# Sheet1.net
KiCad netlist of a schematic drawn in Altium Designer
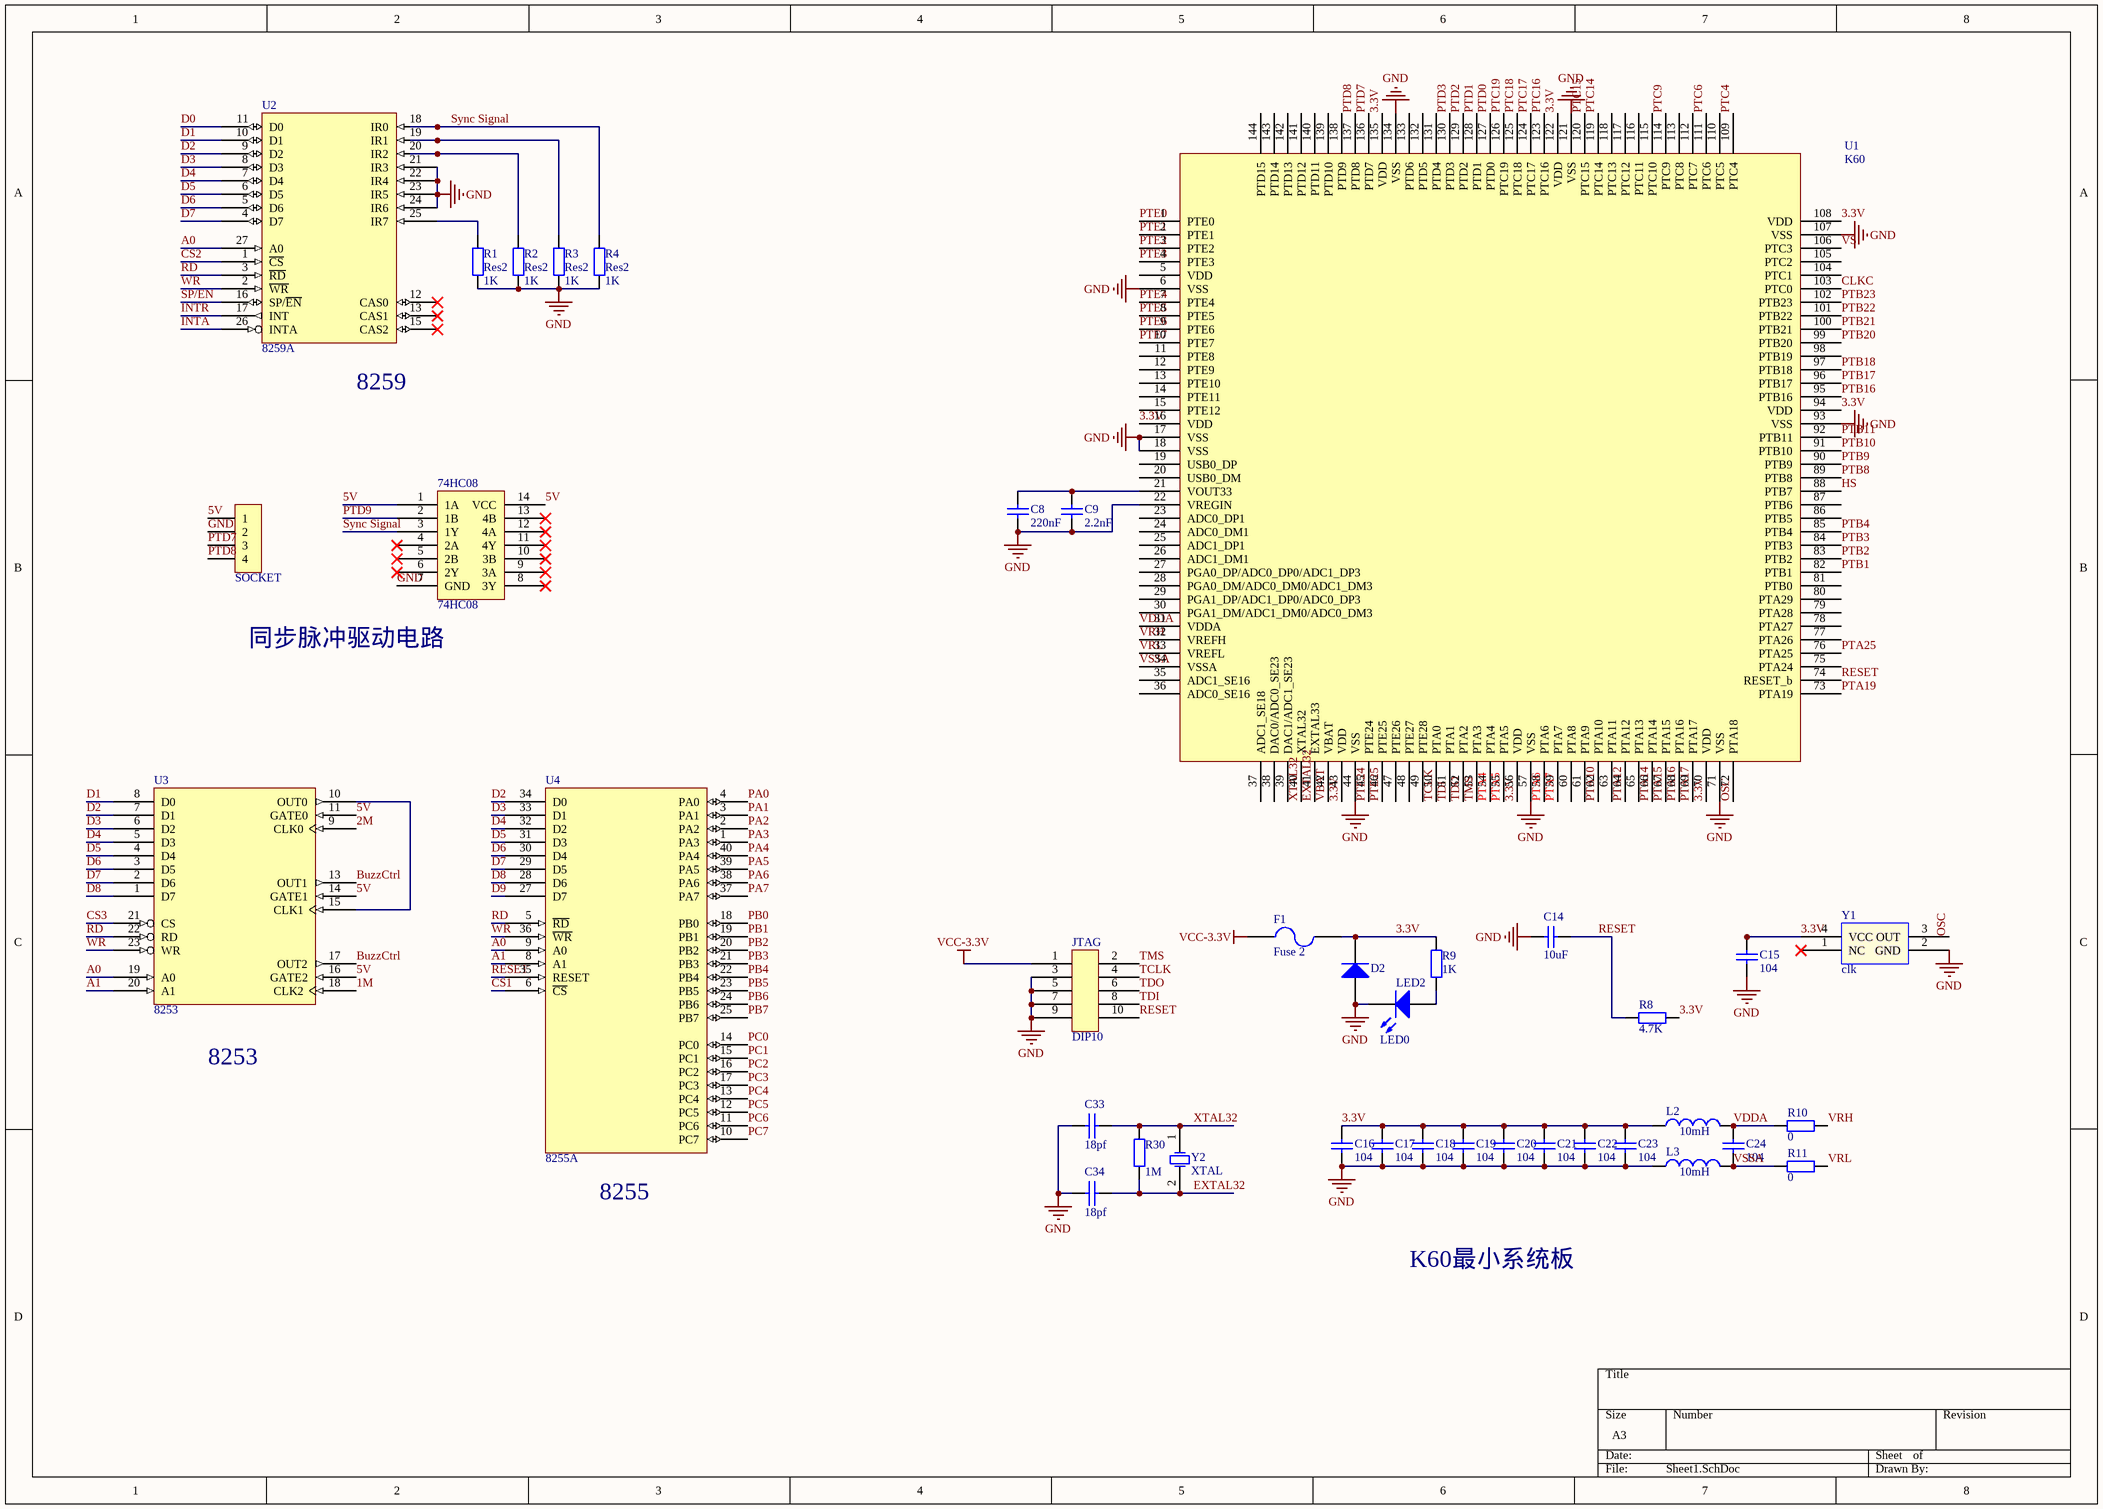
[diagram p0: Sheet1.SchDoc]

(export (version "E")
  (design (tool "Eeschema 10.0.6"))
  (components
    (comp (ref "74HC08") (value "74HC08") (footprint "SO-14") (libsource (lib "主板常用元器件") (part "74HC08")))
    (comp (ref "C8")
      (value "220nF")
      (footprint "0603")
      (description "Capacitor")
      (fields (field (name "Comment") "Cap1") (field (name "PUBLISHER") "Altium Limited"))
      (libsource (lib "主板常用元器件") (part "Cap1"))
    )
    (comp (ref "C9")
      (value "2.2nF")
      (footprint "0603")
      (description "Capacitor")
      (fields (field (name "Comment") "Cap1") (field (name "PUBLISHER") "Altium Limited"))
      (libsource (lib "主板常用元器件") (part "Cap1"))
    )
    (comp (ref "C14")
      (value "10uF")
      (footprint "0603")
      (description "Capacitor")
      (fields (field (name "Comment") "Cap1") (field (name "PUBLISHER") "Altium Limited"))
      (libsource (lib "主板常用元器件") (part "Cap1"))
    )
    (comp (ref "C15")
      (value "104")
      (footprint "0603")
      (description "Capacitor")
      (fields (field (name "Comment") "Cap1") (field (name "PUBLISHER") "Altium Limited"))
      (libsource (lib "主板常用元器件") (part "Cap1"))
    )
    (comp (ref "C16")
      (value "104")
      (footprint "0603")
      (description "Capacitor")
      (fields (field (name "Comment") "Cap1") (field (name "PUBLISHER") "Altium Limited"))
      (libsource (lib "主板常用元器件") (part "Cap1"))
    )
    (comp (ref "C17")
      (value "104")
      (footprint "0603")
      (description "Capacitor")
      (fields (field (name "Comment") "Cap1") (field (name "PUBLISHER") "Altium Limited"))
      (libsource (lib "主板常用元器件") (part "Cap1"))
    )
    (comp (ref "C18")
      (value "104")
      (footprint "0603")
      (description "Capacitor")
      (fields (field (name "Comment") "Cap1") (field (name "PUBLISHER") "Altium Limited"))
      (libsource (lib "主板常用元器件") (part "Cap1"))
    )
    (comp (ref "C19")
      (value "104")
      (footprint "0603")
      (description "Capacitor")
      (fields (field (name "Comment") "Cap1") (field (name "PUBLISHER") "Altium Limited"))
      (libsource (lib "主板常用元器件") (part "Cap1"))
    )
    (comp (ref "C20")
      (value "104")
      (footprint "0603")
      (description "Capacitor")
      (fields (field (name "Comment") "Cap1") (field (name "PUBLISHER") "Altium Limited"))
      (libsource (lib "主板常用元器件") (part "Cap1"))
    )
    (comp (ref "C21")
      (value "104")
      (footprint "0603")
      (description "Capacitor")
      (fields (field (name "Comment") "Cap1") (field (name "PUBLISHER") "Altium Limited"))
      (libsource (lib "主板常用元器件") (part "Cap1"))
    )
    (comp (ref "C22")
      (value "104")
      (footprint "0603")
      (description "Capacitor")
      (fields (field (name "Comment") "Cap1") (field (name "PUBLISHER") "Altium Limited"))
      (libsource (lib "主板常用元器件") (part "Cap1"))
    )
    (comp (ref "C23")
      (value "104")
      (footprint "0603")
      (description "Capacitor")
      (fields (field (name "Comment") "Cap1") (field (name "PUBLISHER") "Altium Limited"))
      (libsource (lib "主板常用元器件") (part "Cap1"))
    )
    (comp (ref "C24")
      (value "104")
      (footprint "0603")
      (description "Capacitor")
      (fields (field (name "Comment") "Cap1") (field (name "PUBLISHER") "Altium Limited"))
      (libsource (lib "主板常用元器件") (part "Cap1"))
    )
    (comp (ref "C33")
      (value "18pf")
      (footprint "0603")
      (description "Capacitor")
      (libsource (lib "easy335schlib") (part "CAP"))
    )
    (comp (ref "C34")
      (value "18pf")
      (footprint "0603")
      (description "Capacitor")
      (libsource (lib "easy335schlib") (part "CAP"))
    )
    (comp (ref "D2")
      (value "Diode")
      (footprint "1206")
      (description "Default Diode")
      (fields (field (name "PUBLISHER") "Altium Limited"))
      (libsource (lib "Miscellaneous Devices") (part "Diode"))
    )
    (comp (ref "F1")
      (value "Fuse 2")
      (footprint "1206")
      (description "Fuse")
      (fields (field (name "PUBLISHER") "Altium Limited"))
      (libsource (lib "Miscellaneous Devices") (part "Fuse 2"))
    )
    (comp (ref "JTAG") (value "DIP10") (footprint "IDC-10") (libsource (lib "主板常用元器件") (part "DIP10")))
    (comp (ref "L2")
      (value "10mH")
      (footprint "0805")
      (description "Inductor")
      (fields (field (name "PUBLISHER") "Altium Limited"))
      (libsource (lib "Miscellaneous Devices") (part "Inductor"))
    )
    (comp (ref "L3")
      (value "10mH")
      (footprint "0805")
      (description "Inductor")
      (fields (field (name "PUBLISHER") "Altium Limited"))
      (libsource (lib "Miscellaneous Devices") (part "Inductor"))
    )
    (comp (ref "LED2")
      (value "LED0")
      (footprint "0603")
      (description "Typical INFRARED GaAs LED")
      (fields (field (name "PUBLISHER") "Altium Limited"))
      (libsource (lib "Miscellaneous Devices") (part "LED0"))
    )
    (comp (ref "R1")
      (value "Res2")
      (footprint "AXIAL-0.4")
      (description "Resistor")
      (fields (field (name "ALTIUM_VALUE") "1K") (field (name "PUBLISHER") "Altium Limited"))
      (libsource (lib "Miscellaneous Devices") (part "Res2"))
    )
    (comp (ref "R2")
      (value "Res2")
      (footprint "AXIAL-0.4")
      (description "Resistor")
      (fields (field (name "ALTIUM_VALUE") "1K") (field (name "PUBLISHER") "Altium Limited"))
      (libsource (lib "Miscellaneous Devices") (part "Res2"))
    )
    (comp (ref "R3")
      (value "Res2")
      (footprint "AXIAL-0.4")
      (description "Resistor")
      (fields (field (name "ALTIUM_VALUE") "1K") (field (name "PUBLISHER") "Altium Limited"))
      (libsource (lib "Miscellaneous Devices") (part "Res2"))
    )
    (comp (ref "R4")
      (value "Res2")
      (footprint "AXIAL-0.4")
      (description "Resistor")
      (fields (field (name "ALTIUM_VALUE") "1K") (field (name "PUBLISHER") "Altium Limited"))
      (libsource (lib "Miscellaneous Devices") (part "Res2"))
    )
    (comp (ref "R8")
      (value "4.7K")
      (footprint "0603")
      (description "Resistor")
      (fields (field (name "Comment") "Res2") (field (name "PUBLISHER") "Altium Limited"))
      (libsource (lib "") (part "Res2_1"))
    )
    (comp (ref "R9")
      (value "1K")
      (footprint "0603")
      (description "Resistor")
      (fields (field (name "Comment") "Res2") (field (name "PUBLISHER") "Altium Limited"))
      (libsource (lib "主板常用元器件") (part "Res2"))
    )
    (comp (ref "R10")
      (value "0")
      (footprint "0603")
      (description "Resistor")
      (fields (field (name "Comment") "Res2") (field (name "PUBLISHER") "Altium Limited"))
      (libsource (lib "") (part "Res2_1"))
    )
    (comp (ref "R11")
      (value "0")
      (footprint "0603")
      (description "Resistor")
      (fields (field (name "Comment") "Res2") (field (name "PUBLISHER") "Altium Limited"))
      (libsource (lib "") (part "Res2_1"))
    )
    (comp (ref "R30")
      (value "1M")
      (footprint "0603")
      (description "Resistor")
      (fields (field (name "Comment") "Res2") (field (name "PUBLISHER") "Altium Limited"))
      (libsource (lib "Miscellaneous Devices") (part "Res2"))
    )
    (comp (ref "U1") (value "K60") (footprint "K60_QFP144") (libsource (lib "*") (part "K60")))
    (comp (ref "U2") (value "8259A") (libsource (lib "Intel 1991-1992") (part "8259A")))
    (comp (ref "U3") (value "8253") (footprint "DIP-24") (libsource (lib "Intel 1991-1992") (part "8253")))
    (comp (ref "U4") (value "8255A") (footprint "DIP-40") (libsource (lib "Intel 1991-1992") (part "8255A")))
    (comp (ref "Y1") (value "clk") (footprint "5032") (libsource (lib "*") (part "clk")))
    (comp (ref "Y2")
      (value "XTAL")
      (footprint "晶振-壳")
      (description "Crystal Oscillator")
      (fields (field (name "PUBLISHER") "Altium Limited"))
      (libsource (lib "Miscellaneous Devices") (part "XTAL"))
    )
    (comp (ref "YY") (value "SOCKET") (footprint "SIP4") (libsource (lib "主板常用元器件") (part "CON4")))
  )
  (nets
    (net (code "1") (name "/1M") (class "Default")
      (node (ref "U3") (pin "18") (pinfunction "CLK2_18") (pintype "input"))
    )
    (net (code "2") (name "/2M") (class "Default")
      (node (ref "U3") (pin "9") (pinfunction "CLK0_9") (pintype "input"))
    )
    (net (code "3") (name "/3.3V") (class "Default")
      (node (ref "C15") (pin "1") (pinfunction "1_1") (pintype "passive"))
      (node (ref "C16") (pin "1") (pinfunction "1_1") (pintype "passive"))
      (node (ref "C17") (pin "1") (pinfunction "1_1") (pintype "passive"))
      (node (ref "C18") (pin "1") (pinfunction "1_1") (pintype "passive"))
      (node (ref "C19") (pin "1") (pinfunction "1_1") (pintype "passive"))
      (node (ref "C20") (pin "1") (pinfunction "1_1") (pintype "passive"))
      (node (ref "C21") (pin "1") (pinfunction "1_1") (pintype "passive"))
      (node (ref "C22") (pin "1") (pinfunction "1_1") (pintype "passive"))
      (node (ref "C23") (pin "1") (pinfunction "1_1") (pintype "passive"))
      (node (ref "D2") (pin "2") (pinfunction "K_2") (pintype "passive"))
      (node (ref "F1") (pin "2") (pinfunction "2_2") (pintype "passive"))
      (node (ref "L2") (pin "1") (pinfunction "1_1") (pintype "passive"))
      (node (ref "R8") (pin "1") (pinfunction "1_1") (pintype "passive"))
      (node (ref "R9") (pin "1") (pinfunction "1_1") (pintype "passive"))
      (node (ref "U1") (pin "108") (pinfunction "VDD_108") (pintype "passive"))
      (node (ref "U1") (pin "122") (pinfunction "VDD_122") (pintype "passive"))
      (node (ref "U1") (pin "135") (pinfunction "VDD_135") (pintype "passive"))
      (node (ref "U1") (pin "16") (pinfunction "VDD_16") (pintype "passive"))
      (node (ref "U1") (pin "43") (pinfunction "VDD_43") (pintype "passive"))
      (node (ref "U1") (pin "56") (pinfunction "VDD_56") (pintype "passive"))
      (node (ref "U1") (pin "70") (pinfunction "VDD_70") (pintype "passive"))
      (node (ref "U1") (pin "94") (pinfunction "VDD_94") (pintype "passive"))
      (node (ref "Y1") (pin "4") (pinfunction "VCC_4") (pintype "passive"))
    )
    (net (code "4") (name "/5V") (class "Default")
      (node (ref "74HC08") (pin "1") (pinfunction "1A_1") (pintype "passive"))
      (node (ref "74HC08") (pin "14") (pinfunction "VCC_14") (pintype "passive"))
      (node (ref "U3") (pin "11") (pinfunction "GATE0_11") (pintype "input"))
      (node (ref "U3") (pin "14") (pinfunction "GATE1_14") (pintype "input"))
      (node (ref "U3") (pin "16") (pinfunction "GATE2_16") (pintype "input"))
      (node (ref "YY") (pin "1") (pinfunction "1_1") (pintype "passive"))
    )
    (net (code "5") (name "/A0") (class "Default")
      (node (ref "U2") (pin "27") (pinfunction "A0_27") (pintype "input"))
      (node (ref "U3") (pin "19") (pinfunction "A0_19") (pintype "input"))
      (node (ref "U4") (pin "9") (pinfunction "A0_9") (pintype "input"))
    )
    (net (code "6") (name "/A1") (class "Default")
      (node (ref "U3") (pin "20") (pinfunction "A1_20") (pintype "input"))
      (node (ref "U4") (pin "8") (pinfunction "A1_8") (pintype "input"))
    )
    (net (code "7") (name "/BuzzCtrl") (class "Default")
      (node (ref "U3") (pin "13") (pinfunction "OUT1_13") (pintype "output"))
      (node (ref "U3") (pin "17") (pinfunction "OUT2_17") (pintype "output"))
    )
    (net (code "8") (name "/CLKC") (class "Default")
      (node (ref "U1") (pin "103") (pinfunction "PTC0_103") (pintype "passive"))
    )
    (net (code "9") (name "/CS1") (class "Default")
      (node (ref "U4") (pin "6") (pinfunction "~{CS}_6") (pintype "input"))
    )
    (net (code "10") (name "/CS2") (class "Default")
      (node (ref "U2") (pin "1") (pinfunction "~{CS}_1") (pintype "input"))
    )
    (net (code "11") (name "/CS3") (class "Default")
      (node (ref "U3") (pin "21") (pinfunction "CS_21") (pintype "input"))
    )
    (net (code "12") (name "/D0") (class "Default")
      (node (ref "U2") (pin "11") (pinfunction "D0_11") (pintype "bidirectional"))
    )
    (net (code "13") (name "/D1") (class "Default")
      (node (ref "U2") (pin "10") (pinfunction "D1_10") (pintype "bidirectional"))
      (node (ref "U3") (pin "8") (pinfunction "D0_8") (pintype "tri_state"))
    )
    (net (code "14") (name "/D2") (class "Default")
      (node (ref "U2") (pin "9") (pinfunction "D2_9") (pintype "bidirectional"))
      (node (ref "U3") (pin "7") (pinfunction "D1_7") (pintype "tri_state"))
      (node (ref "U4") (pin "34") (pinfunction "D0_34") (pintype "tri_state"))
    )
    (net (code "15") (name "/D3") (class "Default")
      (node (ref "U2") (pin "8") (pinfunction "D3_8") (pintype "bidirectional"))
      (node (ref "U3") (pin "6") (pinfunction "D2_6") (pintype "tri_state"))
      (node (ref "U4") (pin "33") (pinfunction "D1_33") (pintype "tri_state"))
    )
    (net (code "16") (name "/D4") (class "Default")
      (node (ref "U2") (pin "7") (pinfunction "D4_7") (pintype "bidirectional"))
      (node (ref "U3") (pin "5") (pinfunction "D3_5") (pintype "tri_state"))
      (node (ref "U4") (pin "32") (pinfunction "D2_32") (pintype "tri_state"))
    )
    (net (code "17") (name "/D5") (class "Default")
      (node (ref "U2") (pin "6") (pinfunction "D5_6") (pintype "bidirectional"))
      (node (ref "U3") (pin "4") (pinfunction "D4_4") (pintype "tri_state"))
      (node (ref "U4") (pin "31") (pinfunction "D3_31") (pintype "tri_state"))
    )
    (net (code "18") (name "/D6") (class "Default")
      (node (ref "U2") (pin "5") (pinfunction "D6_5") (pintype "bidirectional"))
      (node (ref "U3") (pin "3") (pinfunction "D5_3") (pintype "tri_state"))
      (node (ref "U4") (pin "30") (pinfunction "D4_30") (pintype "tri_state"))
    )
    (net (code "19") (name "/D7") (class "Default")
      (node (ref "U2") (pin "4") (pinfunction "D7_4") (pintype "bidirectional"))
      (node (ref "U3") (pin "2") (pinfunction "D6_2") (pintype "tri_state"))
      (node (ref "U4") (pin "29") (pinfunction "D5_29") (pintype "tri_state"))
    )
    (net (code "20") (name "/D8") (class "Default")
      (node (ref "U3") (pin "1") (pinfunction "D7_1") (pintype "tri_state"))
      (node (ref "U4") (pin "28") (pinfunction "D6_28") (pintype "tri_state"))
    )
    (net (code "21") (name "/D9") (class "Default")
      (node (ref "U4") (pin "27") (pinfunction "D7_27") (pintype "tri_state"))
    )
    (net (code "22") (name "/EXTAL32") (class "Default")
      (node (ref "C34") (pin "2") (pinfunction "2_2") (pintype "passive"))
      (node (ref "R30") (pin "1") (pinfunction "1_1") (pintype "passive"))
      (node (ref "U1") (pin "41") (pinfunction "EXTAL33_41") (pintype "passive"))
      (node (ref "Y2") (pin "2") (pinfunction "OSC2_2") (pintype "passive"))
    )
    (net (code "23") (name "/HS") (class "Default")
      (node (ref "U1") (pin "88") (pinfunction "PTB7_88") (pintype "passive"))
    )
    (net (code "24") (name "/INTA") (class "Default")
      (node (ref "U2") (pin "26") (pinfunction "INTA_26") (pintype "input"))
    )
    (net (code "25") (name "/INTR") (class "Default")
      (node (ref "U2") (pin "17") (pinfunction "INT_17") (pintype "output"))
    )
    (net (code "26") (name "/OSC") (class "Default")
      (node (ref "U1") (pin "72") (pinfunction "PTA18_72") (pintype "passive"))
      (node (ref "Y1") (pin "3") (pinfunction "OUT_3") (pintype "passive"))
    )
    (net (code "27") (name "/PA0") (class "Default")
      (node (ref "U4") (pin "4") (pinfunction "PA0_4") (pintype "bidirectional"))
    )
    (net (code "28") (name "/PA1") (class "Default")
      (node (ref "U4") (pin "3") (pinfunction "PA1_3") (pintype "bidirectional"))
    )
    (net (code "29") (name "/PA2") (class "Default")
      (node (ref "U4") (pin "2") (pinfunction "PA2_2") (pintype "bidirectional"))
    )
    (net (code "30") (name "/PA3") (class "Default")
      (node (ref "U4") (pin "1") (pinfunction "PA3_1") (pintype "bidirectional"))
    )
    (net (code "31") (name "/PA4") (class "Default")
      (node (ref "U4") (pin "40") (pinfunction "PA4_40") (pintype "bidirectional"))
    )
    (net (code "32") (name "/PA5") (class "Default")
      (node (ref "U4") (pin "39") (pinfunction "PA5_39") (pintype "bidirectional"))
    )
    (net (code "33") (name "/PA6") (class "Default")
      (node (ref "U4") (pin "38") (pinfunction "PA6_38") (pintype "bidirectional"))
    )
    (net (code "34") (name "/PA7") (class "Default")
      (node (ref "U4") (pin "37") (pinfunction "PA7_37") (pintype "bidirectional"))
    )
    (net (code "35") (name "/PB0") (class "Default")
      (node (ref "U4") (pin "18") (pinfunction "PB0_18") (pintype "bidirectional"))
    )
    (net (code "36") (name "/PB1") (class "Default")
      (node (ref "U4") (pin "19") (pinfunction "PB1_19") (pintype "bidirectional"))
    )
    (net (code "37") (name "/PB2") (class "Default")
      (node (ref "U4") (pin "20") (pinfunction "PB2_20") (pintype "bidirectional"))
    )
    (net (code "38") (name "/PB3") (class "Default")
      (node (ref "U4") (pin "21") (pinfunction "PB3_21") (pintype "bidirectional"))
    )
    (net (code "39") (name "/PB4") (class "Default")
      (node (ref "U4") (pin "22") (pinfunction "PB4_22") (pintype "bidirectional"))
    )
    (net (code "40") (name "/PB5") (class "Default")
      (node (ref "U4") (pin "23") (pinfunction "PB5_23") (pintype "bidirectional"))
    )
    (net (code "41") (name "/PB6") (class "Default")
      (node (ref "U4") (pin "24") (pinfunction "PB6_24") (pintype "bidirectional"))
    )
    (net (code "42") (name "/PB7") (class "Default")
      (node (ref "U4") (pin "25") (pinfunction "PB7_25") (pintype "bidirectional"))
    )
    (net (code "43") (name "/PC0") (class "Default")
      (node (ref "U4") (pin "14") (pinfunction "PC0_14") (pintype "bidirectional"))
    )
    (net (code "44") (name "/PC1") (class "Default")
      (node (ref "U4") (pin "15") (pinfunction "PC1_15") (pintype "bidirectional"))
    )
    (net (code "45") (name "/PC2") (class "Default")
      (node (ref "U4") (pin "16") (pinfunction "PC2_16") (pintype "bidirectional"))
    )
    (net (code "46") (name "/PC3") (class "Default")
      (node (ref "U4") (pin "17") (pinfunction "PC3_17") (pintype "bidirectional"))
    )
    (net (code "47") (name "/PC4") (class "Default")
      (node (ref "U4") (pin "13") (pinfunction "PC4_13") (pintype "bidirectional"))
    )
    (net (code "48") (name "/PC5") (class "Default")
      (node (ref "U4") (pin "12") (pinfunction "PC5_12") (pintype "bidirectional"))
    )
    (net (code "49") (name "/PC6") (class "Default")
      (node (ref "U4") (pin "11") (pinfunction "PC6_11") (pintype "bidirectional"))
    )
    (net (code "50") (name "/PC7") (class "Default")
      (node (ref "U4") (pin "10") (pinfunction "PC7_10") (pintype "bidirectional"))
    )
    (net (code "51") (name "/PTA4") (class "Default")
      (node (ref "U1") (pin "54") (pinfunction "PTA4_54") (pintype "passive"))
    )
    (net (code "52") (name "/PTA5") (class "Default")
      (node (ref "U1") (pin "55") (pinfunction "PTA5_55") (pintype "passive"))
    )
    (net (code "53") (name "/PTA6") (class "Default")
      (node (ref "U1") (pin "58") (pinfunction "PTA6_58") (pintype "passive"))
    )
    (net (code "54") (name "/PTA7") (class "Default")
      (node (ref "U1") (pin "59") (pinfunction "PTA7_59") (pintype "passive"))
    )
    (net (code "55") (name "/PTA10") (class "Default")
      (node (ref "U1") (pin "62") (pinfunction "PTA10_62") (pintype "passive"))
    )
    (net (code "56") (name "/PTA12") (class "Default")
      (node (ref "U1") (pin "64") (pinfunction "PTA12_64") (pintype "passive"))
    )
    (net (code "57") (name "/PTA14") (class "Default")
      (node (ref "U1") (pin "66") (pinfunction "PTA14_66") (pintype "passive"))
    )
    (net (code "58") (name "/PTA15") (class "Default")
      (node (ref "U1") (pin "67") (pinfunction "PTA15_67") (pintype "passive"))
    )
    (net (code "59") (name "/PTA16") (class "Default")
      (node (ref "U1") (pin "68") (pinfunction "PTA16_68") (pintype "passive"))
    )
    (net (code "60") (name "/PTA17") (class "Default")
      (node (ref "U1") (pin "69") (pinfunction "PTA17_69") (pintype "passive"))
    )
    (net (code "61") (name "/PTA19") (class "Default")
      (node (ref "U1") (pin "73") (pinfunction "PTA19_73") (pintype "passive"))
    )
    (net (code "62") (name "/PTA25") (class "Default")
      (node (ref "U1") (pin "76") (pinfunction "PTA25_76") (pintype "passive"))
    )
    (net (code "63") (name "/PTB1") (class "Default")
      (node (ref "U1") (pin "82") (pinfunction "PTB1_82") (pintype "passive"))
    )
    (net (code "64") (name "/PTB2") (class "Default")
      (node (ref "U1") (pin "83") (pinfunction "PTB2_83") (pintype "passive"))
    )
    (net (code "65") (name "/PTB3") (class "Default")
      (node (ref "U1") (pin "84") (pinfunction "PTB3_84") (pintype "passive"))
    )
    (net (code "66") (name "/PTB4") (class "Default")
      (node (ref "U1") (pin "85") (pinfunction "PTB4_85") (pintype "passive"))
    )
    (net (code "67") (name "/PTB8") (class "Default")
      (node (ref "U1") (pin "89") (pinfunction "PTB8_89") (pintype "passive"))
    )
    (net (code "68") (name "/PTB9") (class "Default")
      (node (ref "U1") (pin "90") (pinfunction "PTB9_90") (pintype "passive"))
    )
    (net (code "69") (name "/PTB10") (class "Default")
      (node (ref "U1") (pin "91") (pinfunction "PTB10_91") (pintype "passive"))
    )
    (net (code "70") (name "/PTB11") (class "Default")
      (node (ref "U1") (pin "92") (pinfunction "PTB11_92") (pintype "passive"))
    )
    (net (code "71") (name "/PTB16") (class "Default")
      (node (ref "U1") (pin "95") (pinfunction "PTB16_95") (pintype "passive"))
    )
    (net (code "72") (name "/PTB17") (class "Default")
      (node (ref "U1") (pin "96") (pinfunction "PTB17_96") (pintype "passive"))
    )
    (net (code "73") (name "/PTB18") (class "Default")
      (node (ref "U1") (pin "97") (pinfunction "PTB18_97") (pintype "passive"))
    )
    (net (code "74") (name "/PTB20") (class "Default")
      (node (ref "U1") (pin "99") (pinfunction "PTB20_99") (pintype "passive"))
    )
    (net (code "75") (name "/PTB21") (class "Default")
      (node (ref "U1") (pin "100") (pinfunction "PTB21_100") (pintype "passive"))
    )
    (net (code "76") (name "/PTB22") (class "Default")
      (node (ref "U1") (pin "101") (pinfunction "PTB22_101") (pintype "passive"))
    )
    (net (code "77") (name "/PTB23") (class "Default")
      (node (ref "U1") (pin "102") (pinfunction "PTB23_102") (pintype "passive"))
    )
    (net (code "78") (name "/PTC4") (class "Default")
      (node (ref "U1") (pin "109") (pinfunction "PTC4_109") (pintype "passive"))
    )
    (net (code "79") (name "/PTC6") (class "Default")
      (node (ref "U1") (pin "111") (pinfunction "PTC6_111") (pintype "passive"))
    )
    (net (code "80") (name "/PTC9") (class "Default")
      (node (ref "U1") (pin "114") (pinfunction "PTC9_114") (pintype "passive"))
    )
    (net (code "81") (name "/PTC14") (class "Default")
      (node (ref "U1") (pin "119") (pinfunction "PTC14_119") (pintype "passive"))
    )
    (net (code "82") (name "/PTC15") (class "Default")
      (node (ref "U1") (pin "120") (pinfunction "PTC15_120") (pintype "passive"))
    )
    (net (code "83") (name "/PTC16") (class "Default")
      (node (ref "U1") (pin "123") (pinfunction "PTC16_123") (pintype "passive"))
    )
    (net (code "84") (name "/PTC17") (class "Default")
      (node (ref "U1") (pin "124") (pinfunction "PTC17_124") (pintype "passive"))
    )
    (net (code "85") (name "/PTC18") (class "Default")
      (node (ref "U1") (pin "125") (pinfunction "PTC18_125") (pintype "passive"))
    )
    (net (code "86") (name "/PTC19") (class "Default")
      (node (ref "U1") (pin "126") (pinfunction "PTC19_126") (pintype "passive"))
    )
    (net (code "87") (name "/PTD0") (class "Default")
      (node (ref "U1") (pin "127") (pinfunction "PTD0_127") (pintype "passive"))
    )
    (net (code "88") (name "/PTD1") (class "Default")
      (node (ref "U1") (pin "128") (pinfunction "PTD1_128") (pintype "passive"))
    )
    (net (code "89") (name "/PTD2") (class "Default")
      (node (ref "U1") (pin "129") (pinfunction "PTD2_129") (pintype "passive"))
    )
    (net (code "90") (name "/PTD3") (class "Default")
      (node (ref "U1") (pin "130") (pinfunction "PTD3_130") (pintype "passive"))
    )
    (net (code "91") (name "/PTD7") (class "Default")
      (node (ref "U1") (pin "136") (pinfunction "PTD7_136") (pintype "passive"))
      (node (ref "YY") (pin "3") (pinfunction "3_3") (pintype "passive"))
    )
    (net (code "92") (name "/PTD8") (class "Default")
      (node (ref "U1") (pin "137") (pinfunction "PTD8_137") (pintype "passive"))
      (node (ref "YY") (pin "4") (pinfunction "4_4") (pintype "passive"))
    )
    (net (code "93") (name "/PTD9") (class "Default")
      (node (ref "74HC08") (pin "2") (pinfunction "1B_2") (pintype "passive"))
    )
    (net (code "94") (name "/PTE0") (class "Default")
      (node (ref "U1") (pin "1") (pinfunction "PTE0_1") (pintype "passive"))
    )
    (net (code "95") (name "/PTE1") (class "Default")
      (node (ref "U1") (pin "2") (pinfunction "PTE1_2") (pintype "passive"))
    )
    (net (code "96") (name "/PTE2") (class "Default")
      (node (ref "U1") (pin "3") (pinfunction "PTE2_3") (pintype "passive"))
    )
    (net (code "97") (name "/PTE3") (class "Default")
      (node (ref "U1") (pin "4") (pinfunction "PTE3_4") (pintype "passive"))
    )
    (net (code "98") (name "/PTE4") (class "Default")
      (node (ref "U1") (pin "7") (pinfunction "PTE4_7") (pintype "passive"))
    )
    (net (code "99") (name "/PTE5") (class "Default")
      (node (ref "U1") (pin "8") (pinfunction "PTE5_8") (pintype "passive"))
    )
    (net (code "100") (name "/PTE6") (class "Default")
      (node (ref "U1") (pin "9") (pinfunction "PTE6_9") (pintype "passive"))
    )
    (net (code "101") (name "/PTE7") (class "Default")
      (node (ref "U1") (pin "10") (pinfunction "PTE7_10") (pintype "passive"))
    )
    (net (code "102") (name "/PTE24") (class "Default")
      (node (ref "U1") (pin "45") (pinfunction "PTE24_45") (pintype "passive"))
    )
    (net (code "103") (name "/PTE25") (class "Default")
      (node (ref "U1") (pin "46") (pinfunction "PTE25_46") (pintype "passive"))
    )
    (net (code "104") (name "/RD") (class "Default")
      (node (ref "U2") (pin "3") (pinfunction "~{RD}_3") (pintype "input"))
      (node (ref "U3") (pin "22") (pinfunction "RD_22") (pintype "input"))
      (node (ref "U4") (pin "5") (pinfunction "~{RD}_5") (pintype "input"))
    )
    (net (code "105") (name "/RESET") (class "Default")
      (node (ref "C14") (pin "2") (pinfunction "2_2") (pintype "passive"))
      (node (ref "JTAG") (pin "10") (pinfunction "10_10") (pintype "passive"))
      (node (ref "R8") (pin "2") (pinfunction "2_2") (pintype "passive"))
      (node (ref "U1") (pin "74") (pinfunction "RESET_b_74") (pintype "passive"))
      (node (ref "U4") (pin "35") (pinfunction "RESET_35") (pintype "input"))
    )
    (net (code "106") (name "/SP{slash}EN") (class "Default")
      (node (ref "U2") (pin "16") (pinfunction "SP/~{EN}_16") (pintype "bidirectional"))
    )
    (net (code "107") (name "/Sync Signal") (class "Default")
      (node (ref "74HC08") (pin "3") (pinfunction "1Y_3") (pintype "passive"))
      (node (ref "R4") (pin "2") (pinfunction "2_2") (pintype "passive"))
      (node (ref "U2") (pin "18") (pinfunction "IR0_18") (pintype "input"))
    )
    (net (code "108") (name "/TCLK") (class "Default")
      (node (ref "JTAG") (pin "4") (pinfunction "4_4") (pintype "passive"))
      (node (ref "U1") (pin "50") (pinfunction "PTA0_50") (pintype "passive"))
    )
    (net (code "109") (name "/TDI") (class "Default")
      (node (ref "JTAG") (pin "8") (pinfunction "8_8") (pintype "passive"))
      (node (ref "U1") (pin "51") (pinfunction "PTA1_51") (pintype "passive"))
    )
    (net (code "110") (name "/TDO") (class "Default")
      (node (ref "JTAG") (pin "6") (pinfunction "6_6") (pintype "passive"))
      (node (ref "U1") (pin "52") (pinfunction "PTA2_52") (pintype "passive"))
    )
    (net (code "111") (name "/TMS") (class "Default")
      (node (ref "JTAG") (pin "2") (pinfunction "2_2") (pintype "passive"))
      (node (ref "U1") (pin "53") (pinfunction "PTA3_53") (pintype "passive"))
    )
    (net (code "112") (name "/VBAT") (class "Default")
      (node (ref "U1") (pin "42") (pinfunction "VBAT_42") (pintype "passive"))
    )
    (net (code "113") (name "/VDDA") (class "Default")
      (node (ref "C24") (pin "1") (pinfunction "1_1") (pintype "passive"))
      (node (ref "L2") (pin "2") (pinfunction "2_2") (pintype "passive"))
      (node (ref "R10") (pin "2") (pinfunction "2_2") (pintype "passive"))
      (node (ref "U1") (pin "31") (pinfunction "VDDA_31") (pintype "passive"))
    )
    (net (code "114") (name "/VRH") (class "Default")
      (node (ref "R10") (pin "1") (pinfunction "1_1") (pintype "passive"))
      (node (ref "U1") (pin "32") (pinfunction "VREFH_32") (pintype "passive"))
    )
    (net (code "115") (name "/VRL") (class "Default")
      (node (ref "R11") (pin "1") (pinfunction "1_1") (pintype "passive"))
      (node (ref "U1") (pin "33") (pinfunction "VREFL_33") (pintype "passive"))
    )
    (net (code "116") (name "/VS") (class "Default")
      (node (ref "U1") (pin "106") (pinfunction "PTC3_106") (pintype "passive"))
    )
    (net (code "117") (name "/VSSA") (class "Default")
      (node (ref "C24") (pin "2") (pinfunction "2_2") (pintype "passive"))
      (node (ref "L3") (pin "2") (pinfunction "2_2") (pintype "passive"))
      (node (ref "R11") (pin "2") (pinfunction "2_2") (pintype "passive"))
      (node (ref "U1") (pin "34") (pinfunction "VSSA_34") (pintype "passive"))
    )
    (net (code "118") (name "/WR") (class "Default")
      (node (ref "U2") (pin "2") (pinfunction "~{WR}_2") (pintype "input"))
      (node (ref "U3") (pin "23") (pinfunction "WR_23") (pintype "input"))
      (node (ref "U4") (pin "36") (pinfunction "~{WR}_36") (pintype "input"))
    )
    (net (code "119") (name "/XTAL32") (class "Default")
      (node (ref "C33") (pin "2") (pinfunction "2_2") (pintype "passive"))
      (node (ref "R30") (pin "2") (pinfunction "2_2") (pintype "passive"))
      (node (ref "U1") (pin "40") (pinfunction "XTAL32_40") (pintype "passive"))
      (node (ref "Y2") (pin "1") (pinfunction "OSC1_1") (pintype "passive"))
    )
    (net (code "120") (name "GND") (class "Default")
      (node (ref "74HC08") (pin "7") (pinfunction "GND_7") (pintype "passive"))
      (node (ref "C14") (pin "1") (pinfunction "1_1") (pintype "passive"))
      (node (ref "C15") (pin "2") (pinfunction "2_2") (pintype "passive"))
      (node (ref "C16") (pin "2") (pinfunction "2_2") (pintype "passive"))
      (node (ref "C17") (pin "2") (pinfunction "2_2") (pintype "passive"))
      (node (ref "C18") (pin "2") (pinfunction "2_2") (pintype "passive"))
      (node (ref "C19") (pin "2") (pinfunction "2_2") (pintype "passive"))
      (node (ref "C20") (pin "2") (pinfunction "2_2") (pintype "passive"))
      (node (ref "C21") (pin "2") (pinfunction "2_2") (pintype "passive"))
      (node (ref "C22") (pin "2") (pinfunction "2_2") (pintype "passive"))
      (node (ref "C23") (pin "2") (pinfunction "2_2") (pintype "passive"))
      (node (ref "C33") (pin "1") (pinfunction "1_1") (pintype "passive"))
      (node (ref "C34") (pin "1") (pinfunction "1_1") (pintype "passive"))
      (node (ref "C8") (pin "1") (pinfunction "1_1") (pintype "passive"))
      (node (ref "C9") (pin "1") (pinfunction "1_1") (pintype "passive"))
      (node (ref "D2") (pin "1") (pinfunction "A_1") (pintype "passive"))
      (node (ref "JTAG") (pin "3") (pinfunction "3_3") (pintype "passive"))
      (node (ref "JTAG") (pin "5") (pinfunction "5_5") (pintype "passive"))
      (node (ref "JTAG") (pin "7") (pinfunction "7_7") (pintype "passive"))
      (node (ref "JTAG") (pin "9") (pinfunction "9_9") (pintype "passive"))
      (node (ref "L3") (pin "1") (pinfunction "1_1") (pintype "passive"))
      (node (ref "LED2") (pin "2") (pinfunction "K_2") (pintype "passive"))
      (node (ref "R1") (pin "1") (pinfunction "1_1") (pintype "passive"))
      (node (ref "R2") (pin "1") (pinfunction "1_1") (pintype "passive"))
      (node (ref "R3") (pin "1") (pinfunction "1_1") (pintype "passive"))
      (node (ref "R4") (pin "1") (pinfunction "1_1") (pintype "passive"))
      (node (ref "U1") (pin "107") (pinfunction "VSS_107") (pintype "passive"))
      (node (ref "U1") (pin "121") (pinfunction "VSS_121") (pintype "passive"))
      (node (ref "U1") (pin "134") (pinfunction "VSS_134") (pintype "passive"))
      (node (ref "U1") (pin "17") (pinfunction "VSS_17") (pintype "passive"))
      (node (ref "U1") (pin "18") (pinfunction "VSS_18") (pintype "passive"))
      (node (ref "U1") (pin "22") (pinfunction "VREGIN_22") (pintype "passive"))
      (node (ref "U1") (pin "44") (pinfunction "VSS_44") (pintype "passive"))
      (node (ref "U1") (pin "57") (pinfunction "VSS_57") (pintype "passive"))
      (node (ref "U1") (pin "6") (pinfunction "VSS_6") (pintype "passive"))
      (node (ref "U1") (pin "71") (pinfunction "VSS_71") (pintype "passive"))
      (node (ref "U1") (pin "93") (pinfunction "VSS_93") (pintype "passive"))
      (node (ref "U2") (pin "14") (pinfunction "GND_14") (pintype "power_in"))
      (node (ref "U2") (pin "21") (pinfunction "IR3_21") (pintype "input"))
      (node (ref "U2") (pin "22") (pinfunction "IR4_22") (pintype "input"))
      (node (ref "U2") (pin "23") (pinfunction "IR5_23") (pintype "input"))
      (node (ref "U2") (pin "24") (pinfunction "IR6_24") (pintype "input"))
      (node (ref "U3") (pin "12") (pinfunction "GND_12") (pintype "power_in"))
      (node (ref "U4") (pin "7") (pinfunction "GND_7") (pintype "power_in"))
      (node (ref "Y1") (pin "2") (pinfunction "GND_2") (pintype "passive"))
      (node (ref "YY") (pin "2") (pinfunction "2_2") (pintype "passive"))
    )
    (net (code "121") (name "Net-(LED2-A)") (class "Default")
      (node (ref "LED2") (pin "1") (pinfunction "A_1") (pintype "passive"))
      (node (ref "R9") (pin "2") (pinfunction "2_2") (pintype "passive"))
    )
    (net (code "122") (name "Net-(U1-VOUT33)") (class "Default")
      (node (ref "C8") (pin "2") (pinfunction "2_2") (pintype "passive"))
      (node (ref "C9") (pin "2") (pinfunction "2_2") (pintype "passive"))
      (node (ref "U1") (pin "21") (pinfunction "VOUT33_21") (pintype "passive"))
    )
    (net (code "123") (name "Net-(U2-IR1)") (class "Default")
      (node (ref "R3") (pin "2") (pinfunction "2_2") (pintype "passive"))
      (node (ref "U2") (pin "19") (pinfunction "IR1_19") (pintype "input"))
    )
    (net (code "124") (name "Net-(U2-IR2)") (class "Default")
      (node (ref "R2") (pin "2") (pinfunction "2_2") (pintype "passive"))
      (node (ref "U2") (pin "20") (pinfunction "IR2_20") (pintype "input"))
    )
    (net (code "125") (name "Net-(U2-IR7)") (class "Default")
      (node (ref "R1") (pin "2") (pinfunction "2_2") (pintype "passive"))
      (node (ref "U2") (pin "25") (pinfunction "IR7_25") (pintype "input"))
    )
    (net (code "126") (name "Net-(U3-CLK1)") (class "Default")
      (node (ref "U3") (pin "10") (pinfunction "OUT0_10") (pintype "output"))
      (node (ref "U3") (pin "15") (pinfunction "CLK1_15") (pintype "input"))
    )
    (net (code "127") (name "VCC") (class "Default")
      (node (ref "U2") (pin "28") (pinfunction "VCC_28") (pintype "power_in"))
      (node (ref "U3") (pin "24") (pinfunction "VCC_24") (pintype "power_in"))
      (node (ref "U4") (pin "26") (pinfunction "VCC_26") (pintype "power_in"))
    )
    (net (code "128") (name "VCC-3.3V") (class "Default")
      (node (ref "F1") (pin "1") (pinfunction "1_1") (pintype "passive"))
      (node (ref "JTAG") (pin "1") (pinfunction "1_1") (pintype "passive"))
    )
    (net (code "129") (name "unconnected-(74HC08-2A-Pad4)") (class "Default")
      (node (ref "74HC08") (pin "4") (pinfunction "2A_4") (pintype "passive+no_connect"))
    )
    (net (code "130") (name "unconnected-(74HC08-2B-Pad5)") (class "Default")
      (node (ref "74HC08") (pin "5") (pinfunction "2B_5") (pintype "passive+no_connect"))
    )
    (net (code "131") (name "unconnected-(74HC08-2Y-Pad6)") (class "Default")
      (node (ref "74HC08") (pin "6") (pinfunction "2Y_6") (pintype "passive+no_connect"))
    )
    (net (code "132") (name "unconnected-(74HC08-3A-Pad9)") (class "Default")
      (node (ref "74HC08") (pin "9") (pinfunction "3A_9") (pintype "passive+no_connect"))
    )
    (net (code "133") (name "unconnected-(74HC08-3B-Pad10)") (class "Default")
      (node (ref "74HC08") (pin "10") (pinfunction "3B_10") (pintype "passive+no_connect"))
    )
    (net (code "134") (name "unconnected-(74HC08-3Y-Pad8)") (class "Default")
      (node (ref "74HC08") (pin "8") (pinfunction "3Y_8") (pintype "passive+no_connect"))
    )
    (net (code "135") (name "unconnected-(74HC08-4A-Pad12)") (class "Default")
      (node (ref "74HC08") (pin "12") (pinfunction "4A_12") (pintype "passive+no_connect"))
    )
    (net (code "136") (name "unconnected-(74HC08-4B-Pad13)") (class "Default")
      (node (ref "74HC08") (pin "13") (pinfunction "4B_13") (pintype "passive+no_connect"))
    )
    (net (code "137") (name "unconnected-(74HC08-4Y-Pad11)") (class "Default")
      (node (ref "74HC08") (pin "11") (pinfunction "4Y_11") (pintype "passive+no_connect"))
    )
    (net (code "138") (name "unconnected-(U1-ADC0_DM1-Pad24)") (class "Default")
      (node (ref "U1") (pin "24") (pinfunction "ADC0_DM1_24") (pintype "passive"))
    )
    (net (code "139") (name "unconnected-(U1-ADC0_DP1-Pad23)") (class "Default")
      (node (ref "U1") (pin "23") (pinfunction "ADC0_DP1_23") (pintype "passive"))
    )
    (net (code "140") (name "unconnected-(U1-ADC0_SE16-Pad36)") (class "Default")
      (node (ref "U1") (pin "36") (pinfunction "ADC0_SE16_36") (pintype "passive"))
    )
    (net (code "141") (name "unconnected-(U1-ADC1_DM1-Pad26)") (class "Default")
      (node (ref "U1") (pin "26") (pinfunction "ADC1_DM1_26") (pintype "passive"))
    )
    (net (code "142") (name "unconnected-(U1-ADC1_DP1-Pad25)") (class "Default")
      (node (ref "U1") (pin "25") (pinfunction "ADC1_DP1_25") (pintype "passive"))
    )
    (net (code "143") (name "unconnected-(U1-ADC1_SE16-Pad35)") (class "Default")
      (node (ref "U1") (pin "35") (pinfunction "ADC1_SE16_35") (pintype "passive"))
    )
    (net (code "144") (name "unconnected-(U1-ADC1_SE18-Pad37)") (class "Default")
      (node (ref "U1") (pin "37") (pinfunction "ADC1_SE18_37") (pintype "passive"))
    )
    (net (code "145") (name "unconnected-(U1-DAC0{slash}ADC0_SE23-Pad38)") (class "Default")
      (node (ref "U1") (pin "38") (pinfunction "DAC0/ADC0_SE23_38") (pintype "passive"))
    )
    (net (code "146") (name "unconnected-(U1-DAC1{slash}ADC1_SE23-Pad39)") (class "Default")
      (node (ref "U1") (pin "39") (pinfunction "DAC1/ADC1_SE23_39") (pintype "passive"))
    )
    (net (code "147") (name "unconnected-(U1-PGA0_DM{slash}ADC0_DM0{slash}ADC1_DM3-Pad28)") (class "Default")
      (node (ref "U1") (pin "28") (pinfunction "PGA0_DM/ADC0_DM0/ADC1_DM3_28") (pintype "passive"))
    )
    (net (code "148") (name "unconnected-(U1-PGA0_DP{slash}ADC0_DP0{slash}ADC1_DP3-Pad27)") (class "Default")
      (node (ref "U1") (pin "27") (pinfunction "PGA0_DP/ADC0_DP0/ADC1_DP3_27") (pintype "passive"))
    )
    (net (code "149") (name "unconnected-(U1-PGA1_DM{slash}ADC1_DM0{slash}ADC0_DM3-Pad30)") (class "Default")
      (node (ref "U1") (pin "30") (pinfunction "PGA1_DM/ADC1_DM0/ADC0_DM3_30") (pintype "passive"))
    )
    (net (code "150") (name "unconnected-(U1-PGA1_DP{slash}ADC1_DP0{slash}ADC0_DP3-Pad29)") (class "Default")
      (node (ref "U1") (pin "29") (pinfunction "PGA1_DP/ADC1_DP0/ADC0_DP3_29") (pintype "passive"))
    )
    (net (code "151") (name "unconnected-(U1-PTA8-Pad60)") (class "Default")
      (node (ref "U1") (pin "60") (pinfunction "PTA8_60") (pintype "passive"))
    )
    (net (code "152") (name "unconnected-(U1-PTA9-Pad61)") (class "Default")
      (node (ref "U1") (pin "61") (pinfunction "PTA9_61") (pintype "passive"))
    )
    (net (code "153") (name "unconnected-(U1-PTA11-Pad63)") (class "Default")
      (node (ref "U1") (pin "63") (pinfunction "PTA11_63") (pintype "passive"))
    )
    (net (code "154") (name "unconnected-(U1-PTA13-Pad65)") (class "Default")
      (node (ref "U1") (pin "65") (pinfunction "PTA13_65") (pintype "passive"))
    )
    (net (code "155") (name "unconnected-(U1-PTA24-Pad75)") (class "Default")
      (node (ref "U1") (pin "75") (pinfunction "PTA24_75") (pintype "passive"))
    )
    (net (code "156") (name "unconnected-(U1-PTA26-Pad77)") (class "Default")
      (node (ref "U1") (pin "77") (pinfunction "PTA26_77") (pintype "passive"))
    )
    (net (code "157") (name "unconnected-(U1-PTA27-Pad78)") (class "Default")
      (node (ref "U1") (pin "78") (pinfunction "PTA27_78") (pintype "passive"))
    )
    (net (code "158") (name "unconnected-(U1-PTA28-Pad79)") (class "Default")
      (node (ref "U1") (pin "79") (pinfunction "PTA28_79") (pintype "passive"))
    )
    (net (code "159") (name "unconnected-(U1-PTA29-Pad80)") (class "Default")
      (node (ref "U1") (pin "80") (pinfunction "PTA29_80") (pintype "passive"))
    )
    (net (code "160") (name "unconnected-(U1-PTB0-Pad81)") (class "Default")
      (node (ref "U1") (pin "81") (pinfunction "PTB0_81") (pintype "passive"))
    )
    (net (code "161") (name "unconnected-(U1-PTB5-Pad86)") (class "Default")
      (node (ref "U1") (pin "86") (pinfunction "PTB5_86") (pintype "passive"))
    )
    (net (code "162") (name "unconnected-(U1-PTB6-Pad87)") (class "Default")
      (node (ref "U1") (pin "87") (pinfunction "PTB6_87") (pintype "passive"))
    )
    (net (code "163") (name "unconnected-(U1-PTB19-Pad98)") (class "Default")
      (node (ref "U1") (pin "98") (pinfunction "PTB19_98") (pintype "passive"))
    )
    (net (code "164") (name "unconnected-(U1-PTC1-Pad104)") (class "Default")
      (node (ref "U1") (pin "104") (pinfunction "PTC1_104") (pintype "passive"))
    )
    (net (code "165") (name "unconnected-(U1-PTC2-Pad105)") (class "Default")
      (node (ref "U1") (pin "105") (pinfunction "PTC2_105") (pintype "passive"))
    )
    (net (code "166") (name "unconnected-(U1-PTC5-Pad110)") (class "Default")
      (node (ref "U1") (pin "110") (pinfunction "PTC5_110") (pintype "passive"))
    )
    (net (code "167") (name "unconnected-(U1-PTC7-Pad112)") (class "Default")
      (node (ref "U1") (pin "112") (pinfunction "PTC7_112") (pintype "passive"))
    )
    (net (code "168") (name "unconnected-(U1-PTC8-Pad113)") (class "Default")
      (node (ref "U1") (pin "113") (pinfunction "PTC8_113") (pintype "passive"))
    )
    (net (code "169") (name "unconnected-(U1-PTC10-Pad115)") (class "Default")
      (node (ref "U1") (pin "115") (pinfunction "PTC10_115") (pintype "passive"))
    )
    (net (code "170") (name "unconnected-(U1-PTC11-Pad116)") (class "Default")
      (node (ref "U1") (pin "116") (pinfunction "PTC11_116") (pintype "passive"))
    )
    (net (code "171") (name "unconnected-(U1-PTC12-Pad117)") (class "Default")
      (node (ref "U1") (pin "117") (pinfunction "PTC12_117") (pintype "passive"))
    )
    (net (code "172") (name "unconnected-(U1-PTC13-Pad118)") (class "Default")
      (node (ref "U1") (pin "118") (pinfunction "PTC13_118") (pintype "passive"))
    )
    (net (code "173") (name "unconnected-(U1-PTD4-Pad131)") (class "Default")
      (node (ref "U1") (pin "131") (pinfunction "PTD4_131") (pintype "passive"))
    )
    (net (code "174") (name "unconnected-(U1-PTD5-Pad132)") (class "Default")
      (node (ref "U1") (pin "132") (pinfunction "PTD5_132") (pintype "passive"))
    )
    (net (code "175") (name "unconnected-(U1-PTD6-Pad133)") (class "Default")
      (node (ref "U1") (pin "133") (pinfunction "PTD6_133") (pintype "passive"))
    )
    (net (code "176") (name "unconnected-(U1-PTD9-Pad138)") (class "Default")
      (node (ref "U1") (pin "138") (pinfunction "PTD9_138") (pintype "passive"))
    )
    (net (code "177") (name "unconnected-(U1-PTD10-Pad139)") (class "Default")
      (node (ref "U1") (pin "139") (pinfunction "PTD10_139") (pintype "passive"))
    )
    (net (code "178") (name "unconnected-(U1-PTD11-Pad140)") (class "Default")
      (node (ref "U1") (pin "140") (pinfunction "PTD11_140") (pintype "passive"))
    )
    (net (code "179") (name "unconnected-(U1-PTD12-Pad141)") (class "Default")
      (node (ref "U1") (pin "141") (pinfunction "PTD12_141") (pintype "passive"))
    )
    (net (code "180") (name "unconnected-(U1-PTD13-Pad142)") (class "Default")
      (node (ref "U1") (pin "142") (pinfunction "PTD13_142") (pintype "passive"))
    )
    (net (code "181") (name "unconnected-(U1-PTD14-Pad143)") (class "Default")
      (node (ref "U1") (pin "143") (pinfunction "PTD14_143") (pintype "passive"))
    )
    (net (code "182") (name "unconnected-(U1-PTD15-Pad144)") (class "Default")
      (node (ref "U1") (pin "144") (pinfunction "PTD15_144") (pintype "passive"))
    )
    (net (code "183") (name "unconnected-(U1-PTE8-Pad11)") (class "Default")
      (node (ref "U1") (pin "11") (pinfunction "PTE8_11") (pintype "passive"))
    )
    (net (code "184") (name "unconnected-(U1-PTE9-Pad12)") (class "Default")
      (node (ref "U1") (pin "12") (pinfunction "PTE9_12") (pintype "passive"))
    )
    (net (code "185") (name "unconnected-(U1-PTE10-Pad13)") (class "Default")
      (node (ref "U1") (pin "13") (pinfunction "PTE10_13") (pintype "passive"))
    )
    (net (code "186") (name "unconnected-(U1-PTE11-Pad14)") (class "Default")
      (node (ref "U1") (pin "14") (pinfunction "PTE11_14") (pintype "passive"))
    )
    (net (code "187") (name "unconnected-(U1-PTE12-Pad15)") (class "Default")
      (node (ref "U1") (pin "15") (pinfunction "PTE12_15") (pintype "passive"))
    )
    (net (code "188") (name "unconnected-(U1-PTE26-Pad47)") (class "Default")
      (node (ref "U1") (pin "47") (pinfunction "PTE26_47") (pintype "passive"))
    )
    (net (code "189") (name "unconnected-(U1-PTE27-Pad48)") (class "Default")
      (node (ref "U1") (pin "48") (pinfunction "PTE27_48") (pintype "passive"))
    )
    (net (code "190") (name "unconnected-(U1-PTE28-Pad49)") (class "Default")
      (node (ref "U1") (pin "49") (pinfunction "PTE28_49") (pintype "passive"))
    )
    (net (code "191") (name "unconnected-(U1-USB0_DM-Pad20)") (class "Default")
      (node (ref "U1") (pin "20") (pinfunction "USB0_DM_20") (pintype "passive"))
    )
    (net (code "192") (name "unconnected-(U1-USB0_DP-Pad19)") (class "Default")
      (node (ref "U1") (pin "19") (pinfunction "USB0_DP_19") (pintype "passive"))
    )
    (net (code "193") (name "unconnected-(U1-VDD-Pad5)") (class "Default")
      (node (ref "U1") (pin "5") (pinfunction "VDD_5") (pintype "passive"))
    )
    (net (code "194") (name "unconnected-(U2-CAS0-Pad12)") (class "Default")
      (node (ref "U2") (pin "12") (pinfunction "CAS0_12") (pintype "bidirectional+no_connect"))
    )
    (net (code "195") (name "unconnected-(U2-CAS1-Pad13)") (class "Default")
      (node (ref "U2") (pin "13") (pinfunction "CAS1_13") (pintype "bidirectional+no_connect"))
    )
    (net (code "196") (name "unconnected-(U2-CAS2-Pad15)") (class "Default")
      (node (ref "U2") (pin "15") (pinfunction "CAS2_15") (pintype "bidirectional+no_connect"))
    )
    (net (code "197") (name "unconnected-(Y1-NC-Pad1)") (class "Default")
      (node (ref "Y1") (pin "1") (pinfunction "NC_1") (pintype "passive+no_connect"))
    )
  )
)
